# Ethernet_Switch.net
KiCad netlist of a schematic drawn in Altium Designer
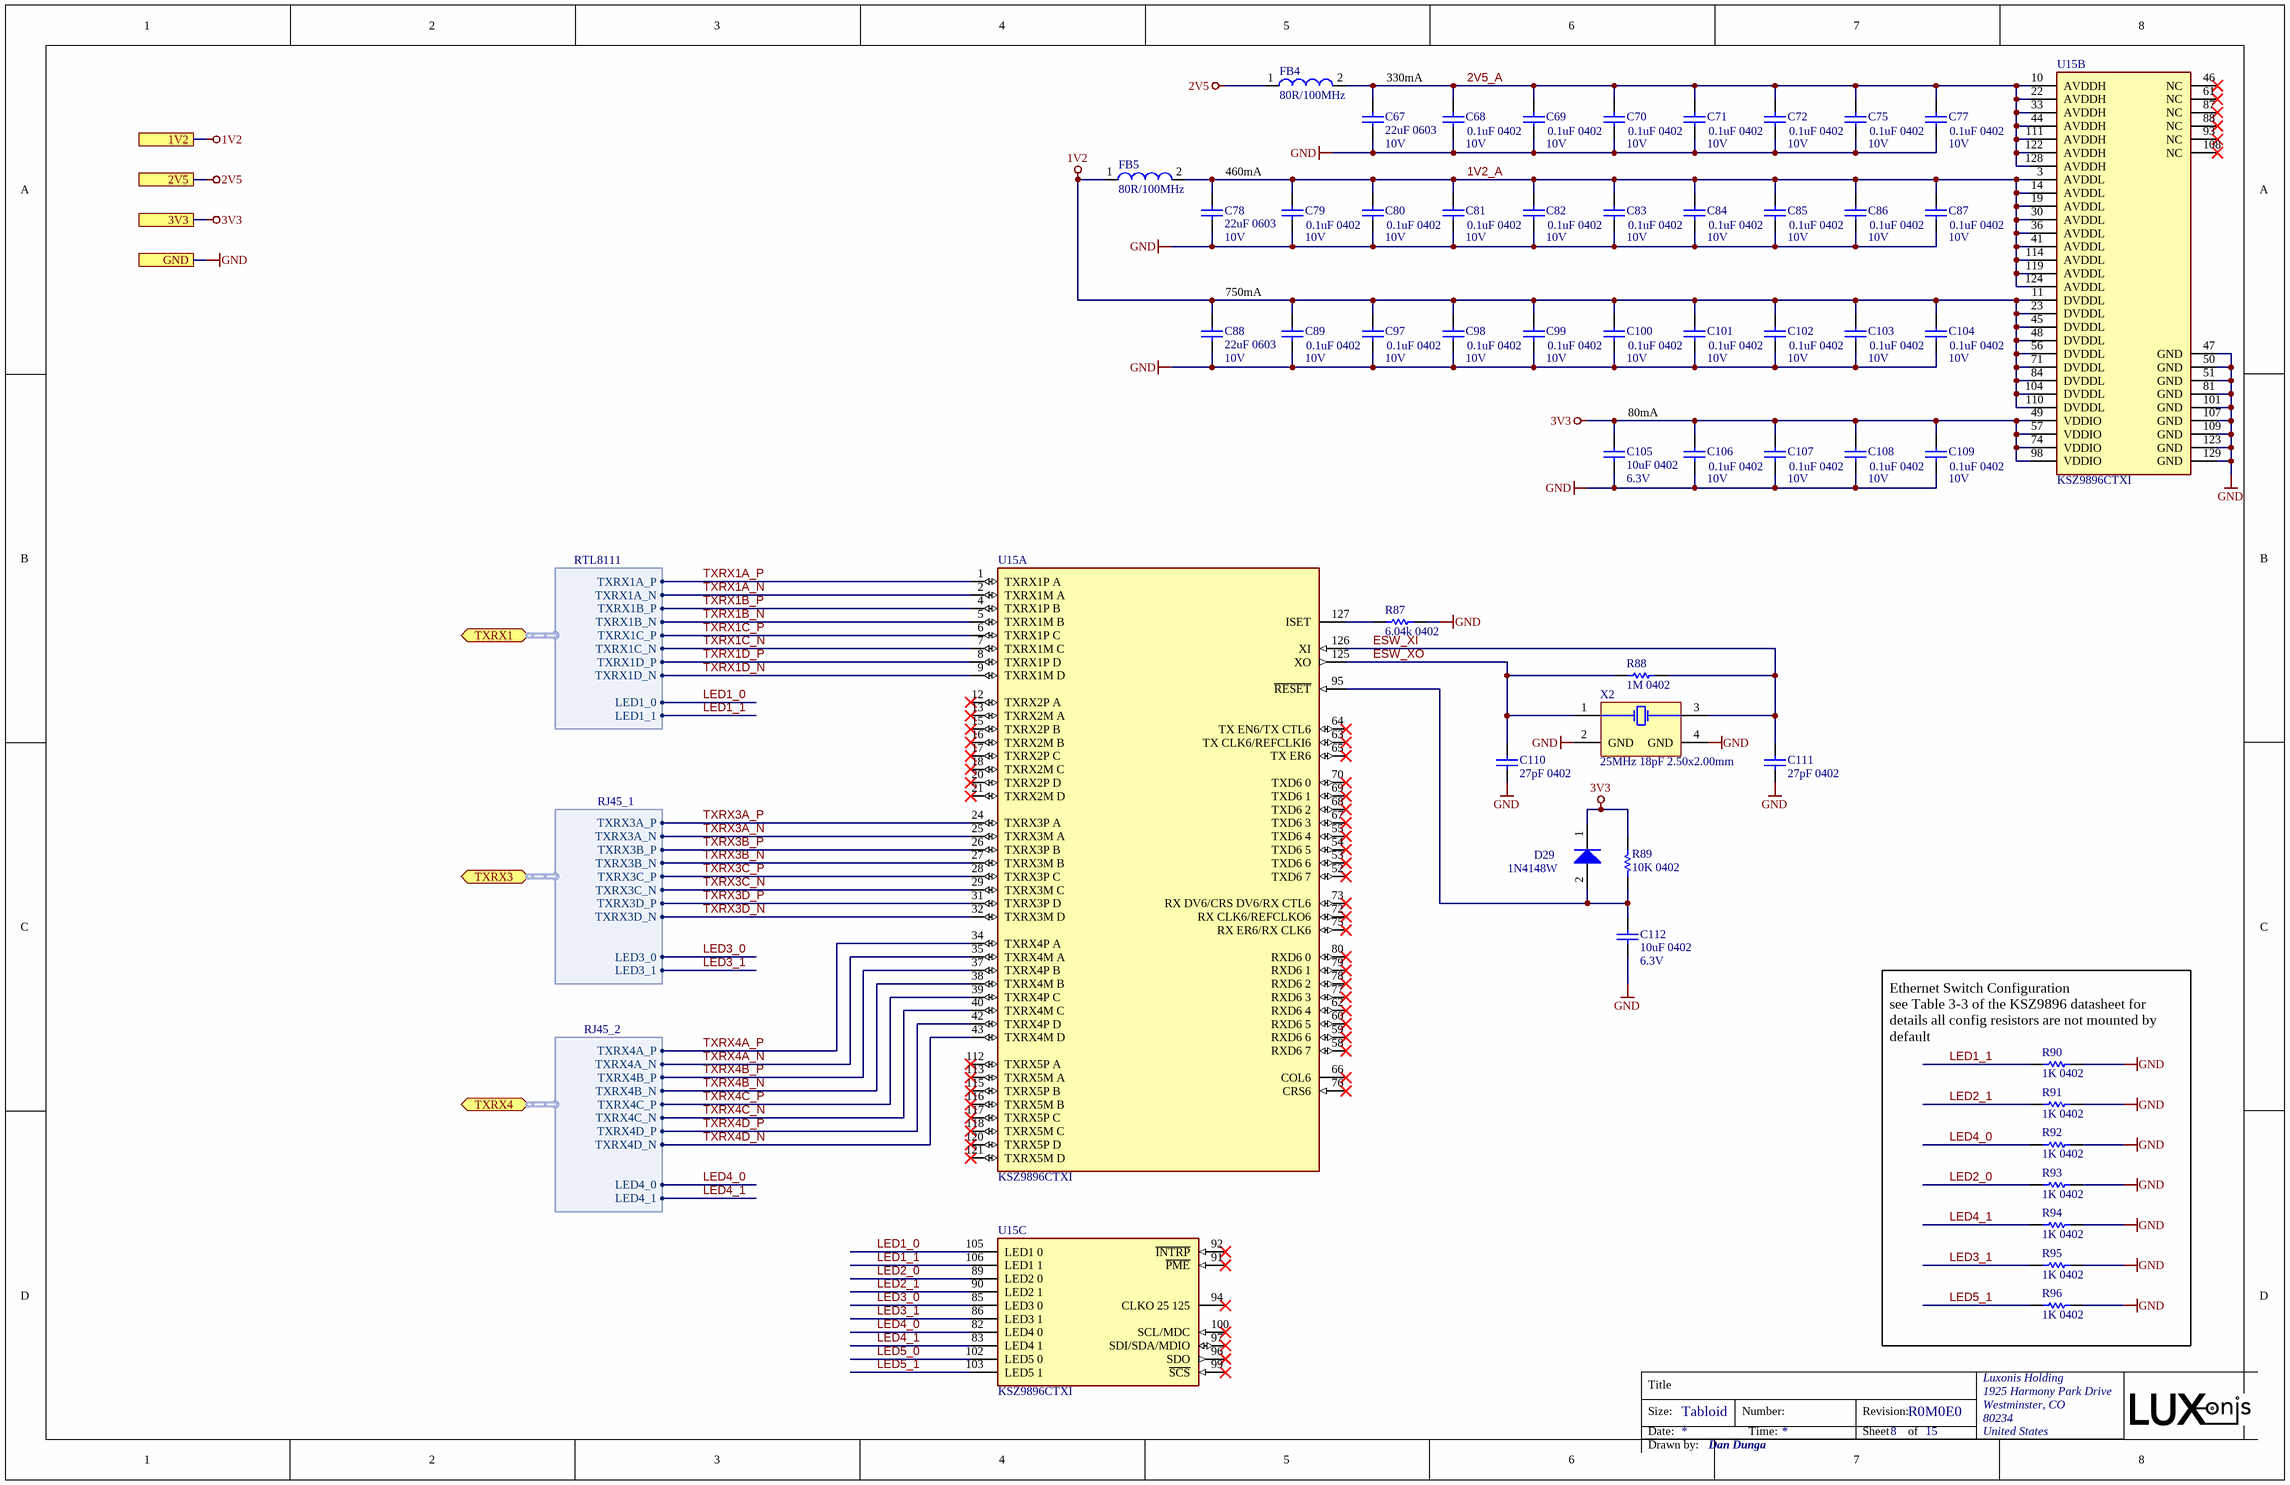
[diagram p0: Ethernet_Switch.SchDoc]

(export (version "E")
  (design (tool "Eeschema 10.0.6"))
  (components
    (comp (ref "C67")
      (value "22uF 0603")
      (footprint "CAPC0603(1608)100_N")
      (description "CAP CER 22UF 10V X5R 0603 20%")
      (fields (field (name "TOLERANCE") "20%") (field (name "VOLTAGE RATING") "10V"))
      (libsource (lib "LuxonisMaster") (part "GRM188R61A226ME15D"))
    )
    (comp (ref "C68")
      (value "0.1uF 0402")
      (footprint "CAPC0402(1005)70_N")
      (description "CAP CER 0.1UF 10V X7R 0402 5%")
      (fields (field (name "TOLERANCE") "5%") (field (name "VOLTAGE RATING") "10V"))
      (libsource (lib "LuxonisMaster") (part "GRM155R71A104JA01D"))
    )
    (comp (ref "C69")
      (value "0.1uF 0402")
      (footprint "CAPC0402(1005)70_N")
      (description "CAP CER 0.1UF 10V X7R 0402 5%")
      (fields (field (name "TOLERANCE") "5%") (field (name "VOLTAGE RATING") "10V"))
      (libsource (lib "LuxonisMaster") (part "GRM155R71A104JA01D"))
    )
    (comp (ref "C70")
      (value "0.1uF 0402")
      (footprint "CAPC0402(1005)70_N")
      (description "CAP CER 0.1UF 10V X7R 0402 5%")
      (fields (field (name "TOLERANCE") "5%") (field (name "VOLTAGE RATING") "10V"))
      (libsource (lib "LuxonisMaster") (part "GRM155R71A104JA01D"))
    )
    (comp (ref "C71")
      (value "0.1uF 0402")
      (footprint "CAPC0402(1005)70_N")
      (description "CAP CER 0.1UF 10V X7R 0402 5%")
      (fields (field (name "TOLERANCE") "5%") (field (name "VOLTAGE RATING") "10V"))
      (libsource (lib "LuxonisMaster") (part "GRM155R71A104JA01D"))
    )
    (comp (ref "C72")
      (value "0.1uF 0402")
      (footprint "CAPC0402(1005)70_N")
      (description "CAP CER 0.1UF 10V X7R 0402 5%")
      (fields (field (name "TOLERANCE") "5%") (field (name "VOLTAGE RATING") "10V"))
      (libsource (lib "LuxonisMaster") (part "GRM155R71A104JA01D"))
    )
    (comp (ref "C75")
      (value "0.1uF 0402")
      (footprint "CAPC0402(1005)70_N")
      (description "CAP CER 0.1UF 10V X7R 0402 5%")
      (fields (field (name "TOLERANCE") "5%") (field (name "VOLTAGE RATING") "10V"))
      (libsource (lib "LuxonisMaster") (part "GRM155R71A104JA01D"))
    )
    (comp (ref "C77")
      (value "0.1uF 0402")
      (footprint "CAPC0402(1005)70_N")
      (description "CAP CER 0.1UF 10V X7R 0402 5%")
      (fields (field (name "TOLERANCE") "5%") (field (name "VOLTAGE RATING") "10V"))
      (libsource (lib "LuxonisMaster") (part "GRM155R71A104JA01D"))
    )
    (comp (ref "C78")
      (value "22uF 0603")
      (footprint "CAPC0603(1608)100_N")
      (description "CAP CER 22UF 10V X5R 0603 20%")
      (fields (field (name "TOLERANCE") "20%") (field (name "VOLTAGE RATING") "10V"))
      (libsource (lib "LuxonisMaster") (part "GRM188R61A226ME15D"))
    )
    (comp (ref "C79")
      (value "0.1uF 0402")
      (footprint "CAPC0402(1005)70_N")
      (description "CAP CER 0.1UF 10V X7R 0402 5%")
      (fields (field (name "TOLERANCE") "5%") (field (name "VOLTAGE RATING") "10V"))
      (libsource (lib "LuxonisMaster") (part "GRM155R71A104JA01D"))
    )
    (comp (ref "C80")
      (value "0.1uF 0402")
      (footprint "CAPC0402(1005)70_N")
      (description "CAP CER 0.1UF 10V X7R 0402 5%")
      (fields (field (name "TOLERANCE") "5%") (field (name "VOLTAGE RATING") "10V"))
      (libsource (lib "LuxonisMaster") (part "GRM155R71A104JA01D"))
    )
    (comp (ref "C81")
      (value "0.1uF 0402")
      (footprint "CAPC0402(1005)70_N")
      (description "CAP CER 0.1UF 10V X7R 0402 5%")
      (fields (field (name "TOLERANCE") "5%") (field (name "VOLTAGE RATING") "10V"))
      (libsource (lib "LuxonisMaster") (part "GRM155R71A104JA01D"))
    )
    (comp (ref "C82")
      (value "0.1uF 0402")
      (footprint "CAPC0402(1005)70_N")
      (description "CAP CER 0.1UF 10V X7R 0402 5%")
      (fields (field (name "TOLERANCE") "5%") (field (name "VOLTAGE RATING") "10V"))
      (libsource (lib "LuxonisMaster") (part "GRM155R71A104JA01D"))
    )
    (comp (ref "C83")
      (value "0.1uF 0402")
      (footprint "CAPC0402(1005)70_N")
      (description "CAP CER 0.1UF 10V X7R 0402 5%")
      (fields (field (name "TOLERANCE") "5%") (field (name "VOLTAGE RATING") "10V"))
      (libsource (lib "LuxonisMaster") (part "GRM155R71A104JA01D"))
    )
    (comp (ref "C84")
      (value "0.1uF 0402")
      (footprint "CAPC0402(1005)70_N")
      (description "CAP CER 0.1UF 10V X7R 0402 5%")
      (fields (field (name "TOLERANCE") "5%") (field (name "VOLTAGE RATING") "10V"))
      (libsource (lib "LuxonisMaster") (part "GRM155R71A104JA01D"))
    )
    (comp (ref "C85")
      (value "0.1uF 0402")
      (footprint "CAPC0402(1005)70_N")
      (description "CAP CER 0.1UF 10V X7R 0402 5%")
      (fields (field (name "TOLERANCE") "5%") (field (name "VOLTAGE RATING") "10V"))
      (libsource (lib "LuxonisMaster") (part "GRM155R71A104JA01D"))
    )
    (comp (ref "C86")
      (value "0.1uF 0402")
      (footprint "CAPC0402(1005)70_N")
      (description "CAP CER 0.1UF 10V X7R 0402 5%")
      (fields (field (name "TOLERANCE") "5%") (field (name "VOLTAGE RATING") "10V"))
      (libsource (lib "LuxonisMaster") (part "GRM155R71A104JA01D"))
    )
    (comp (ref "C87")
      (value "0.1uF 0402")
      (footprint "CAPC0402(1005)70_N")
      (description "CAP CER 0.1UF 10V X7R 0402 5%")
      (fields (field (name "TOLERANCE") "5%") (field (name "VOLTAGE RATING") "10V"))
      (libsource (lib "LuxonisMaster") (part "GRM155R71A104JA01D"))
    )
    (comp (ref "C88")
      (value "22uF 0603")
      (footprint "CAPC0603(1608)100_N")
      (description "CAP CER 22UF 10V X5R 0603 20%")
      (fields (field (name "TOLERANCE") "20%") (field (name "VOLTAGE RATING") "10V"))
      (libsource (lib "LuxonisMaster") (part "GRM188R61A226ME15D"))
    )
    (comp (ref "C89")
      (value "0.1uF 0402")
      (footprint "CAPC0402(1005)70_N")
      (description "CAP CER 0.1UF 10V X7R 0402 5%")
      (fields (field (name "TOLERANCE") "5%") (field (name "VOLTAGE RATING") "10V"))
      (libsource (lib "LuxonisMaster") (part "GRM155R71A104JA01D"))
    )
    (comp (ref "C97")
      (value "0.1uF 0402")
      (footprint "CAPC0402(1005)70_N")
      (description "CAP CER 0.1UF 10V X7R 0402 5%")
      (fields (field (name "TOLERANCE") "5%") (field (name "VOLTAGE RATING") "10V"))
      (libsource (lib "LuxonisMaster") (part "GRM155R71A104JA01D"))
    )
    (comp (ref "C98")
      (value "0.1uF 0402")
      (footprint "CAPC0402(1005)70_N")
      (description "CAP CER 0.1UF 10V X7R 0402 5%")
      (fields (field (name "TOLERANCE") "5%") (field (name "VOLTAGE RATING") "10V"))
      (libsource (lib "LuxonisMaster") (part "GRM155R71A104JA01D"))
    )
    (comp (ref "C99")
      (value "0.1uF 0402")
      (footprint "CAPC0402(1005)70_N")
      (description "CAP CER 0.1UF 10V X7R 0402 5%")
      (fields (field (name "TOLERANCE") "5%") (field (name "VOLTAGE RATING") "10V"))
      (libsource (lib "LuxonisMaster") (part "GRM155R71A104JA01D"))
    )
    (comp (ref "C100")
      (value "0.1uF 0402")
      (footprint "CAPC0402(1005)70_N")
      (description "CAP CER 0.1UF 10V X7R 0402 5%")
      (fields (field (name "TOLERANCE") "5%") (field (name "VOLTAGE RATING") "10V"))
      (libsource (lib "LuxonisMaster") (part "GRM155R71A104JA01D"))
    )
    (comp (ref "C101")
      (value "0.1uF 0402")
      (footprint "CAPC0402(1005)70_N")
      (description "CAP CER 0.1UF 10V X7R 0402 5%")
      (fields (field (name "TOLERANCE") "5%") (field (name "VOLTAGE RATING") "10V"))
      (libsource (lib "LuxonisMaster") (part "GRM155R71A104JA01D"))
    )
    (comp (ref "C102")
      (value "0.1uF 0402")
      (footprint "CAPC0402(1005)70_N")
      (description "CAP CER 0.1UF 10V X7R 0402 5%")
      (fields (field (name "TOLERANCE") "5%") (field (name "VOLTAGE RATING") "10V"))
      (libsource (lib "LuxonisMaster") (part "GRM155R71A104JA01D"))
    )
    (comp (ref "C103")
      (value "0.1uF 0402")
      (footprint "CAPC0402(1005)70_N")
      (description "CAP CER 0.1UF 10V X7R 0402 5%")
      (fields (field (name "TOLERANCE") "5%") (field (name "VOLTAGE RATING") "10V"))
      (libsource (lib "LuxonisMaster") (part "GRM155R71A104JA01D"))
    )
    (comp (ref "C104")
      (value "0.1uF 0402")
      (footprint "CAPC0402(1005)70_N")
      (description "CAP CER 0.1UF 10V X7R 0402 5%")
      (fields (field (name "TOLERANCE") "5%") (field (name "VOLTAGE RATING") "10V"))
      (libsource (lib "LuxonisMaster") (part "GRM155R71A104JA01D"))
    )
    (comp (ref "C105")
      (value "10uF 0402")
      (footprint "CAPC0402(1005)70_N")
      (description "CAP CER 10UF 6.3V X5R 0402 20%")
      (fields (field (name "TOLERANCE") "20%") (field (name "VOLTAGE RATING") "6.3V"))
      (libsource (lib "LuxonisMaster") (part "GRM155R60J106ME15D"))
    )
    (comp (ref "C106")
      (value "0.1uF 0402")
      (footprint "CAPC0402(1005)70_N")
      (description "CAP CER 0.1UF 10V X7R 0402 5%")
      (fields (field (name "TOLERANCE") "5%") (field (name "VOLTAGE RATING") "10V"))
      (libsource (lib "LuxonisMaster") (part "GRM155R71A104JA01D"))
    )
    (comp (ref "C107")
      (value "0.1uF 0402")
      (footprint "CAPC0402(1005)70_N")
      (description "CAP CER 0.1UF 10V X7R 0402 5%")
      (fields (field (name "TOLERANCE") "5%") (field (name "VOLTAGE RATING") "10V"))
      (libsource (lib "LuxonisMaster") (part "GRM155R71A104JA01D"))
    )
    (comp (ref "C108")
      (value "0.1uF 0402")
      (footprint "CAPC0402(1005)70_N")
      (description "CAP CER 0.1UF 10V X7R 0402 5%")
      (fields (field (name "TOLERANCE") "5%") (field (name "VOLTAGE RATING") "10V"))
      (libsource (lib "LuxonisMaster") (part "GRM155R71A104JA01D"))
    )
    (comp (ref "C109")
      (value "0.1uF 0402")
      (footprint "CAPC0402(1005)70_N")
      (description "CAP CER 0.1UF 10V X7R 0402 5%")
      (fields (field (name "TOLERANCE") "5%") (field (name "VOLTAGE RATING") "10V"))
      (libsource (lib "LuxonisMaster") (part "GRM155R71A104JA01D"))
    )
    (comp (ref "C110")
      (value "27pF 0402")
      (footprint "CAPC0402(1005)60_N")
      (description "CAP CER 27PF 50V C0G/NP0 0402")
      (fields (field (name "TOLERANCE") "5%") (field (name "VOLTAGE") "50V"))
      (libsource (lib "BW2098POE") (part "C0402C270J5GACTU"))
    )
    (comp (ref "C111")
      (value "27pF 0402")
      (footprint "CAPC0402(1005)60_N")
      (description "CAP CER 27PF 50V C0G/NP0 0402")
      (fields (field (name "TOLERANCE") "5%") (field (name "VOLTAGE") "50V"))
      (libsource (lib "BW2098POE") (part "C0402C270J5GACTU"))
    )
    (comp (ref "C112")
      (value "10uF 0402")
      (footprint "CAPC0402(1005)70_N")
      (description "CAP CER 10UF 6.3V X5R 0402 20%")
      (fields (field (name "TOLERANCE") "20%") (field (name "VOLTAGE RATING") "6.3V"))
      (libsource (lib "LuxonisMaster") (part "GRM155R60J106ME15D"))
    )
    (comp (ref "D29")
      (value "1N4148W")
      (footprint "1N4148W-7-F")
      (description "DIODE GEN PURP 100V 300MA SOD123")
      (fields (field (name "VOLTAGE") "100V"))
      (libsource (lib "PCBProject") (part "1N4148W-7-F"))
    )
    (comp (ref "FB4")
      (value "80R/100MHz")
      (footprint "BK1608HS800-T_N")
      (description "FERRITE BEAD 80 OHM 0603 1LN")
      (fields (field (name "TOLERANCE") "25%"))
      (libsource (lib "LuxonisMaster") (part "BK1608HS800-T"))
    )
    (comp (ref "FB5")
      (value "80R/100MHz")
      (footprint "BK1608HS800-T_N")
      (description "FERRITE BEAD 80 OHM 0603 1LN")
      (fields (field (name "TOLERANCE") "25%"))
      (libsource (lib "LuxonisMaster") (part "BK1608HS800-T"))
    )
    (comp (ref "R87")
      (value "6.04k 0402")
      (footprint "RESC0402(1005)_L")
      (description "Res Thick Film 0402 6.04K Ohm 1% 0.063W(1/16W) ±100ppm/C Molded SMD Automotive Paper T/R")
      (fields (field (name "TOLERANCE") "1%"))
      (libsource (lib "BW2098POE_Anfa") (part "CRCW04026K04FKED"))
    )
    (comp (ref "R88")
      (value "1M 0402")
      (footprint "RESC0402(1005)_N")
      (description "RES SMD 1M OHM 1% 1/16W 0402")
      (fields (field (name "TOLERANCE") "1%"))
      (libsource (lib "LuxonisMaster") (part "RC0402FR-071ML"))
    )
    (comp (ref "R89")
      (value "10K 0402")
      (footprint "RESC0402(1005)_N")
      (fields (field (name "TOLERANCE") "1%"))
      (libsource (lib "LuxonisMaster") (part "RC0402FR-1310KL"))
    )
    (comp (ref "R90")
      (value "1K 0402")
      (footprint "RESC0402(1005)_N")
      (fields (field (name "TOLERANCE") "1%"))
      (libsource (lib "LuxonisMaster") (part "RC0402FR-071KL"))
    )
    (comp (ref "R91")
      (value "1K 0402")
      (footprint "RESC0402(1005)_N")
      (fields (field (name "TOLERANCE") "1%"))
      (libsource (lib "LuxonisMaster") (part "RC0402FR-071KL"))
    )
    (comp (ref "R92")
      (value "1K 0402")
      (footprint "RESC0402(1005)_N")
      (fields (field (name "TOLERANCE") "1%"))
      (libsource (lib "LuxonisMaster") (part "RC0402FR-071KL"))
    )
    (comp (ref "R93")
      (value "1K 0402")
      (footprint "RESC0402(1005)_N")
      (fields (field (name "TOLERANCE") "1%"))
      (libsource (lib "LuxonisMaster") (part "RC0402FR-071KL"))
    )
    (comp (ref "R94")
      (value "1K 0402")
      (footprint "RESC0402(1005)_N")
      (fields (field (name "TOLERANCE") "1%"))
      (libsource (lib "LuxonisMaster") (part "RC0402FR-071KL"))
    )
    (comp (ref "R95")
      (value "1K 0402")
      (footprint "RESC0402(1005)_N")
      (fields (field (name "TOLERANCE") "1%"))
      (libsource (lib "LuxonisMaster") (part "RC0402FR-071KL"))
    )
    (comp (ref "R96")
      (value "1K 0402")
      (footprint "RESC0402(1005)_N")
      (fields (field (name "TOLERANCE") "1%"))
      (libsource (lib "LuxonisMaster") (part "RC0402FR-071KL"))
    )
    (comp (ref "U15")
      (value "KSZ9896CTXI")
      (footprint "FP-C04-418-IPC_A")
      (description "MICROCHIP - KSZ9896CTXI - ETHERNET SWITCH, 1GBPS, -40 TO 85DEG C")
      (libsource (lib "BW2098POE_Anfa") (part "KSZ9896CTXI"))
    )
    (comp (ref "X2")
      (value "25MHz 18pF 2.50x2.00mm")
      (footprint "ECS-250-18-36B-CKY-TR")
      (description "CRYSTAL 25.0000MHZ 18PF SMD 25MHz ±10ppm Crystal 18pF 50 Ohms 4-SMD, No Lead")
      (libsource (lib "BW2098POE") (part "ECS-250-18-36B-CKY-TR"))
    )
  )
  (nets
    (net (code "4") (name "/1V2_A") (class "Default")
      (node (ref "C78") (pin "2") (pinfunction "2_2") (pintype "passive"))
      (node (ref "C79") (pin "2") (pinfunction "2_2") (pintype "passive"))
      (node (ref "C80") (pin "2") (pinfunction "2_2") (pintype "passive"))
      (node (ref "C81") (pin "2") (pinfunction "2_2") (pintype "passive"))
      (node (ref "C82") (pin "2") (pinfunction "2_2") (pintype "passive"))
      (node (ref "C83") (pin "2") (pinfunction "2_2") (pintype "passive"))
      (node (ref "C84") (pin "2") (pinfunction "2_2") (pintype "passive"))
      (node (ref "C85") (pin "2") (pinfunction "2_2") (pintype "passive"))
      (node (ref "C86") (pin "2") (pinfunction "2_2") (pintype "passive"))
      (node (ref "C87") (pin "2") (pinfunction "2_2") (pintype "passive"))
      (node (ref "FB5") (pin "2") (pinfunction "2_2") (pintype "passive"))
      (node (ref "U15") (pin "114") (pinfunction "AVDDL_114") (pintype "power_in"))
      (node (ref "U15") (pin "119") (pinfunction "AVDDL_119") (pintype "power_in"))
      (node (ref "U15") (pin "124") (pinfunction "AVDDL_124") (pintype "power_in"))
      (node (ref "U15") (pin "14") (pinfunction "AVDDL_14") (pintype "power_in"))
      (node (ref "U15") (pin "19") (pinfunction "AVDDL_19") (pintype "power_in"))
      (node (ref "U15") (pin "3") (pinfunction "AVDDL_3") (pintype "power_in"))
      (node (ref "U15") (pin "30") (pinfunction "AVDDL_30") (pintype "power_in"))
      (node (ref "U15") (pin "36") (pinfunction "AVDDL_36") (pintype "passive"))
      (node (ref "U15") (pin "41") (pinfunction "AVDDL_41") (pintype "power_in"))
    )
    (net (code "5") (name "/2V5_A") (class "Default")
      (node (ref "C67") (pin "2") (pinfunction "2_2") (pintype "passive"))
      (node (ref "C68") (pin "2") (pinfunction "2_2") (pintype "passive"))
      (node (ref "C69") (pin "2") (pinfunction "2_2") (pintype "passive"))
      (node (ref "C70") (pin "2") (pinfunction "2_2") (pintype "passive"))
      (node (ref "C71") (pin "2") (pinfunction "2_2") (pintype "passive"))
      (node (ref "C72") (pin "2") (pinfunction "2_2") (pintype "passive"))
      (node (ref "C75") (pin "2") (pinfunction "2_2") (pintype "passive"))
      (node (ref "C77") (pin "2") (pinfunction "2_2") (pintype "passive"))
      (node (ref "FB4") (pin "2") (pinfunction "2_2") (pintype "passive"))
      (node (ref "U15") (pin "10") (pinfunction "AVDDH_10") (pintype "power_in"))
      (node (ref "U15") (pin "111") (pinfunction "AVDDH_111") (pintype "power_in"))
      (node (ref "U15") (pin "122") (pinfunction "AVDDH_122") (pintype "power_in"))
      (node (ref "U15") (pin "128") (pinfunction "AVDDH_128") (pintype "power_in"))
      (node (ref "U15") (pin "22") (pinfunction "AVDDH_22") (pintype "power_in"))
      (node (ref "U15") (pin "33") (pinfunction "AVDDH_33") (pintype "power_in"))
      (node (ref "U15") (pin "44") (pinfunction "AVDDH_44") (pintype "power_in"))
    )
    (net (code "6") (name "/ESW_XI") (class "Default")
      (node (ref "C111") (pin "2") (pinfunction "2_2") (pintype "passive"))
      (node (ref "R88") (pin "2") (pinfunction "2_2") (pintype "passive"))
      (node (ref "U15") (pin "126") (pinfunction "XI_126") (pintype "input"))
      (node (ref "X2") (pin "3") (pinfunction "X2_3") (pintype "passive"))
    )
    (net (code "7") (name "/ESW_XO") (class "Default")
      (node (ref "C110") (pin "2") (pinfunction "2_2") (pintype "passive"))
      (node (ref "R88") (pin "1") (pinfunction "1_1") (pintype "passive"))
      (node (ref "U15") (pin "125") (pinfunction "XO_125") (pintype "output"))
      (node (ref "X2") (pin "1") (pinfunction "X1_1") (pintype "passive"))
    )
    (net (code "8") (name "/LED1_0") (class "Default")
      (node (ref "U15") (pin "105") (pinfunction "LED1_0_105") (pintype "passive"))
    )
    (net (code "9") (name "/LED1_1") (class "Default")
      (node (ref "R90") (pin "2") (pinfunction "2_2") (pintype "passive"))
      (node (ref "U15") (pin "106") (pinfunction "LED1_1_106") (pintype "passive"))
    )
    (net (code "10") (name "/LED2_0") (class "Default")
      (node (ref "R93") (pin "2") (pinfunction "2_2") (pintype "passive"))
      (node (ref "U15") (pin "89") (pinfunction "LED2_0_89") (pintype "passive"))
    )
    (net (code "11") (name "/LED2_1") (class "Default")
      (node (ref "R91") (pin "2") (pinfunction "2_2") (pintype "passive"))
      (node (ref "U15") (pin "90") (pinfunction "LED2_1_90") (pintype "passive"))
    )
    (net (code "12") (name "/LED3_0") (class "Default")
      (node (ref "U15") (pin "85") (pinfunction "LED3_0_85") (pintype "passive"))
    )
    (net (code "13") (name "/LED3_1") (class "Default")
      (node (ref "R95") (pin "2") (pinfunction "2_2") (pintype "passive"))
      (node (ref "U15") (pin "86") (pinfunction "LED3_1_86") (pintype "passive"))
    )
    (net (code "14") (name "/LED4_0") (class "Default")
      (node (ref "R92") (pin "2") (pinfunction "2_2") (pintype "passive"))
      (node (ref "U15") (pin "82") (pinfunction "LED4_0_82") (pintype "passive"))
    )
    (net (code "15") (name "/LED4_1") (class "Default")
      (node (ref "R94") (pin "2") (pinfunction "2_2") (pintype "passive"))
      (node (ref "U15") (pin "83") (pinfunction "LED4_1_83") (pintype "passive"))
    )
    (net (code "16") (name "/LED5_0") (class "Default")
      (node (ref "U15") (pin "102") (pinfunction "LED5_0_102") (pintype "passive"))
    )
    (net (code "17") (name "/LED5_1") (class "Default")
      (node (ref "R96") (pin "2") (pinfunction "2_2") (pintype "passive"))
      (node (ref "U15") (pin "103") (pinfunction "LED5_1_103") (pintype "passive"))
    )
    (net (code "18") (name "/TXRX1A_N") (class "Default")
      (node (ref "U15") (pin "2") (pinfunction "TXRX1M_A_2") (pintype "bidirectional"))
    )
    (net (code "19") (name "/TXRX1A_P") (class "Default")
      (node (ref "U15") (pin "1") (pinfunction "TXRX1P_A_1") (pintype "bidirectional"))
    )
    (net (code "20") (name "/TXRX1B_N") (class "Default")
      (node (ref "U15") (pin "5") (pinfunction "TXRX1M_B_5") (pintype "bidirectional"))
    )
    (net (code "21") (name "/TXRX1B_P") (class "Default")
      (node (ref "U15") (pin "4") (pinfunction "TXRX1P_B_4") (pintype "bidirectional"))
    )
    (net (code "22") (name "/TXRX1C_N") (class "Default")
      (node (ref "U15") (pin "7") (pinfunction "TXRX1M_C_7") (pintype "bidirectional"))
    )
    (net (code "23") (name "/TXRX1C_P") (class "Default")
      (node (ref "U15") (pin "6") (pinfunction "TXRX1P_C_6") (pintype "bidirectional"))
    )
    (net (code "24") (name "/TXRX1D_N") (class "Default")
      (node (ref "U15") (pin "9") (pinfunction "TXRX1M_D_9") (pintype "bidirectional"))
    )
    (net (code "25") (name "/TXRX1D_P") (class "Default")
      (node (ref "U15") (pin "8") (pinfunction "TXRX1P_D_8") (pintype "bidirectional"))
    )
    (net (code "26") (name "/TXRX3A_N") (class "Default")
      (node (ref "U15") (pin "25") (pinfunction "TXRX3M_A_25") (pintype "bidirectional"))
    )
    (net (code "27") (name "/TXRX3A_P") (class "Default")
      (node (ref "U15") (pin "24") (pinfunction "TXRX3P_A_24") (pintype "bidirectional"))
    )
    (net (code "28") (name "/TXRX3B_N") (class "Default")
      (node (ref "U15") (pin "27") (pinfunction "TXRX3M_B_27") (pintype "bidirectional"))
    )
    (net (code "29") (name "/TXRX3B_P") (class "Default")
      (node (ref "U15") (pin "26") (pinfunction "TXRX3P_B_26") (pintype "bidirectional"))
    )
    (net (code "30") (name "/TXRX3C_N") (class "Default")
      (node (ref "U15") (pin "29") (pinfunction "TXRX3M_C_29") (pintype "bidirectional"))
    )
    (net (code "31") (name "/TXRX3C_P") (class "Default")
      (node (ref "U15") (pin "28") (pinfunction "TXRX3P_C_28") (pintype "bidirectional"))
    )
    (net (code "32") (name "/TXRX3D_N") (class "Default")
      (node (ref "U15") (pin "32") (pinfunction "TXRX3M_D_32") (pintype "bidirectional"))
    )
    (net (code "33") (name "/TXRX3D_P") (class "Default")
      (node (ref "U15") (pin "31") (pinfunction "TXRX3P_D_31") (pintype "bidirectional"))
    )
    (net (code "34") (name "/TXRX4A_N") (class "Default")
      (node (ref "U15") (pin "35") (pinfunction "TXRX4M_A_35") (pintype "bidirectional"))
    )
    (net (code "35") (name "/TXRX4A_P") (class "Default")
      (node (ref "U15") (pin "34") (pinfunction "TXRX4P_A_34") (pintype "bidirectional"))
    )
    (net (code "36") (name "/TXRX4B_N") (class "Default")
      (node (ref "U15") (pin "38") (pinfunction "TXRX4M_B_38") (pintype "bidirectional"))
    )
    (net (code "37") (name "/TXRX4B_P") (class "Default")
      (node (ref "U15") (pin "37") (pinfunction "TXRX4P_B_37") (pintype "bidirectional"))
    )
    (net (code "38") (name "/TXRX4C_N") (class "Default")
      (node (ref "U15") (pin "40") (pinfunction "TXRX4M_C_40") (pintype "bidirectional"))
    )
    (net (code "39") (name "/TXRX4C_P") (class "Default")
      (node (ref "U15") (pin "39") (pinfunction "TXRX4P_C_39") (pintype "bidirectional"))
    )
    (net (code "40") (name "/TXRX4D_N") (class "Default")
      (node (ref "U15") (pin "43") (pinfunction "TXRX4M_D_43") (pintype "bidirectional"))
    )
    (net (code "41") (name "/TXRX4D_P") (class "Default")
      (node (ref "U15") (pin "42") (pinfunction "TXRX4P_D_42") (pintype "bidirectional"))
    )
    (net (code "45") (name "1V2") (class "Default")
      (node (ref "C100") (pin "2") (pinfunction "2_2") (pintype "passive"))
      (node (ref "C101") (pin "2") (pinfunction "2_2") (pintype "passive"))
      (node (ref "C102") (pin "2") (pinfunction "2_2") (pintype "passive"))
      (node (ref "C103") (pin "2") (pinfunction "2_2") (pintype "passive"))
      (node (ref "C104") (pin "2") (pinfunction "2_2") (pintype "passive"))
      (node (ref "C88") (pin "2") (pinfunction "2_2") (pintype "passive"))
      (node (ref "C89") (pin "2") (pinfunction "2_2") (pintype "passive"))
      (node (ref "C97") (pin "2") (pinfunction "2_2") (pintype "passive"))
      (node (ref "C98") (pin "2") (pinfunction "2_2") (pintype "passive"))
      (node (ref "C99") (pin "2") (pinfunction "2_2") (pintype "passive"))
      (node (ref "FB5") (pin "1") (pinfunction "1_1") (pintype "passive"))
      (node (ref "U15") (pin "104") (pinfunction "DVDDL_104") (pintype "power_in"))
      (node (ref "U15") (pin "11") (pinfunction "DVDDL_11") (pintype "power_in"))
      (node (ref "U15") (pin "110") (pinfunction "DVDDL_110") (pintype "power_in"))
      (node (ref "U15") (pin "23") (pinfunction "DVDDL_23") (pintype "power_in"))
      (node (ref "U15") (pin "45") (pinfunction "DVDDL_45") (pintype "power_in"))
      (node (ref "U15") (pin "48") (pinfunction "DVDDL_48") (pintype "power_in"))
      (node (ref "U15") (pin "56") (pinfunction "DVDDL_56") (pintype "power_in"))
      (node (ref "U15") (pin "71") (pinfunction "DVDDL_71") (pintype "power_in"))
      (node (ref "U15") (pin "84") (pinfunction "DVDDL_84") (pintype "power_in"))
    )
    (net (code "46") (name "2V5") (class "Default")
      (node (ref "FB4") (pin "1") (pinfunction "1_1") (pintype "passive"))
    )
    (net (code "47") (name "3V3") (class "Default")
      (node (ref "C105") (pin "2") (pinfunction "2_2") (pintype "passive"))
      (node (ref "C106") (pin "2") (pinfunction "2_2") (pintype "passive"))
      (node (ref "C107") (pin "2") (pinfunction "2_2") (pintype "passive"))
      (node (ref "C108") (pin "2") (pinfunction "2_2") (pintype "passive"))
      (node (ref "C109") (pin "2") (pinfunction "2_2") (pintype "passive"))
      (node (ref "D29") (pin "1") (pinfunction "K_1") (pintype "passive"))
      (node (ref "R89") (pin "1") (pinfunction "1_1") (pintype "passive"))
      (node (ref "U15") (pin "49") (pinfunction "VDDIO_49") (pintype "power_in"))
      (node (ref "U15") (pin "57") (pinfunction "VDDIO_57") (pintype "power_in"))
      (node (ref "U15") (pin "74") (pinfunction "VDDIO_74") (pintype "power_in"))
      (node (ref "U15") (pin "98") (pinfunction "VDDIO_98") (pintype "power_in"))
    )
    (net (code "48") (name "GND") (class "Default")
      (node (ref "C100") (pin "1") (pinfunction "1_1") (pintype "passive"))
      (node (ref "C101") (pin "1") (pinfunction "1_1") (pintype "passive"))
      (node (ref "C102") (pin "1") (pinfunction "1_1") (pintype "passive"))
      (node (ref "C103") (pin "1") (pinfunction "1_1") (pintype "passive"))
      (node (ref "C104") (pin "1") (pinfunction "1_1") (pintype "passive"))
      (node (ref "C105") (pin "1") (pinfunction "1_1") (pintype "passive"))
      (node (ref "C106") (pin "1") (pinfunction "1_1") (pintype "passive"))
      (node (ref "C107") (pin "1") (pinfunction "1_1") (pintype "passive"))
      (node (ref "C108") (pin "1") (pinfunction "1_1") (pintype "passive"))
      (node (ref "C109") (pin "1") (pinfunction "1_1") (pintype "passive"))
      (node (ref "C110") (pin "1") (pinfunction "1_1") (pintype "passive"))
      (node (ref "C111") (pin "1") (pinfunction "1_1") (pintype "passive"))
      (node (ref "C112") (pin "1") (pinfunction "1_1") (pintype "passive"))
      (node (ref "C67") (pin "1") (pinfunction "1_1") (pintype "passive"))
      (node (ref "C68") (pin "1") (pinfunction "1_1") (pintype "passive"))
      (node (ref "C69") (pin "1") (pinfunction "1_1") (pintype "passive"))
      (node (ref "C70") (pin "1") (pinfunction "1_1") (pintype "passive"))
      (node (ref "C71") (pin "1") (pinfunction "1_1") (pintype "passive"))
      (node (ref "C72") (pin "1") (pinfunction "1_1") (pintype "passive"))
      (node (ref "C75") (pin "1") (pinfunction "1_1") (pintype "passive"))
      (node (ref "C77") (pin "1") (pinfunction "1_1") (pintype "passive"))
      (node (ref "C78") (pin "1") (pinfunction "1_1") (pintype "passive"))
      (node (ref "C79") (pin "1") (pinfunction "1_1") (pintype "passive"))
      (node (ref "C80") (pin "1") (pinfunction "1_1") (pintype "passive"))
      (node (ref "C81") (pin "1") (pinfunction "1_1") (pintype "passive"))
      (node (ref "C82") (pin "1") (pinfunction "1_1") (pintype "passive"))
      (node (ref "C83") (pin "1") (pinfunction "1_1") (pintype "passive"))
      (node (ref "C84") (pin "1") (pinfunction "1_1") (pintype "passive"))
      (node (ref "C85") (pin "1") (pinfunction "1_1") (pintype "passive"))
      (node (ref "C86") (pin "1") (pinfunction "1_1") (pintype "passive"))
      (node (ref "C87") (pin "1") (pinfunction "1_1") (pintype "passive"))
      (node (ref "C88") (pin "1") (pinfunction "1_1") (pintype "passive"))
      (node (ref "C89") (pin "1") (pinfunction "1_1") (pintype "passive"))
      (node (ref "C97") (pin "1") (pinfunction "1_1") (pintype "passive"))
      (node (ref "C98") (pin "1") (pinfunction "1_1") (pintype "passive"))
      (node (ref "C99") (pin "1") (pinfunction "1_1") (pintype "passive"))
      (node (ref "R87") (pin "2") (pinfunction "2_2") (pintype "passive"))
      (node (ref "R90") (pin "1") (pinfunction "1_1") (pintype "passive"))
      (node (ref "R91") (pin "1") (pinfunction "1_1") (pintype "passive"))
      (node (ref "R92") (pin "1") (pinfunction "1_1") (pintype "passive"))
      (node (ref "R93") (pin "1") (pinfunction "1_1") (pintype "passive"))
      (node (ref "R94") (pin "1") (pinfunction "1_1") (pintype "passive"))
      (node (ref "R95") (pin "1") (pinfunction "1_1") (pintype "passive"))
      (node (ref "R96") (pin "1") (pinfunction "1_1") (pintype "passive"))
      (node (ref "U15") (pin "101") (pinfunction "GND_101") (pintype "power_in"))
      (node (ref "U15") (pin "107") (pinfunction "GND_107") (pintype "power_in"))
      (node (ref "U15") (pin "109") (pinfunction "GND_109") (pintype "power_in"))
      (node (ref "U15") (pin "123") (pinfunction "GND_123") (pintype "power_in"))
      (node (ref "U15") (pin "129") (pinfunction "GND_129") (pintype "power_in"))
      (node (ref "U15") (pin "47") (pinfunction "GND_47") (pintype "power_in"))
      (node (ref "U15") (pin "50") (pinfunction "GND_50") (pintype "power_in"))
      (node (ref "U15") (pin "51") (pinfunction "GND_51") (pintype "power_in"))
      (node (ref "U15") (pin "81") (pinfunction "GND_81") (pintype "power_in"))
      (node (ref "X2") (pin "2") (pinfunction "GND_2") (pintype "power_in"))
      (node (ref "X2") (pin "4") (pinfunction "GND_4") (pintype "power_in"))
    )
    (net (code "49") (name "Net-(D29-A)") (class "Default")
      (node (ref "C112") (pin "2") (pinfunction "2_2") (pintype "passive"))
      (node (ref "D29") (pin "2") (pinfunction "A_2") (pintype "passive"))
      (node (ref "R89") (pin "2") (pinfunction "2_2") (pintype "passive"))
      (node (ref "U15") (pin "95") (pinfunction "~{RESET}_95") (pintype "input"))
    )
    (net (code "50") (name "Net-(U15A-ISET)") (class "Default")
      (node (ref "R87") (pin "1") (pinfunction "1_1") (pintype "passive"))
      (node (ref "U15") (pin "127") (pinfunction "ISET_127") (pintype "passive"))
    )
    (net (code "51") (name "unconnected-(U15A-COL6-Pad66)") (class "Default")
      (node (ref "U15") (pin "66") (pinfunction "COL6_66") (pintype "passive+no_connect"))
    )
    (net (code "52") (name "unconnected-(U15A-CRS6-Pad76)") (class "Default")
      (node (ref "U15") (pin "76") (pinfunction "CRS6_76") (pintype "input+no_connect"))
    )
    (net (code "53") (name "unconnected-(U15A-RXD6_0-Pad80)") (class "Default")
      (node (ref "U15") (pin "80") (pinfunction "RXD6_0_80") (pintype "bidirectional+no_connect"))
    )
    (net (code "54") (name "unconnected-(U15A-RXD6_1-Pad79)") (class "Default")
      (node (ref "U15") (pin "79") (pinfunction "RXD6_1_79") (pintype "bidirectional+no_connect"))
    )
    (net (code "55") (name "unconnected-(U15A-RXD6_2-Pad78)") (class "Default")
      (node (ref "U15") (pin "78") (pinfunction "RXD6_2_78") (pintype "bidirectional+no_connect"))
    )
    (net (code "56") (name "unconnected-(U15A-RXD6_3-Pad77)") (class "Default")
      (node (ref "U15") (pin "77") (pinfunction "RXD6_3_77") (pintype "bidirectional+no_connect"))
    )
    (net (code "57") (name "unconnected-(U15A-RXD6_4-Pad62)") (class "Default")
      (node (ref "U15") (pin "62") (pinfunction "RXD6_4_62") (pintype "bidirectional+no_connect"))
    )
    (net (code "58") (name "unconnected-(U15A-RXD6_5-Pad60)") (class "Default")
      (node (ref "U15") (pin "60") (pinfunction "RXD6_5_60") (pintype "bidirectional+no_connect"))
    )
    (net (code "59") (name "unconnected-(U15A-RXD6_6-Pad59)") (class "Default")
      (node (ref "U15") (pin "59") (pinfunction "RXD6_6_59") (pintype "bidirectional+no_connect"))
    )
    (net (code "60") (name "unconnected-(U15A-RXD6_7-Pad58)") (class "Default")
      (node (ref "U15") (pin "58") (pinfunction "RXD6_7_58") (pintype "bidirectional+no_connect"))
    )
    (net (code "61") (name "unconnected-(U15A-RX_CLK6{slash}REFCLKO6-Pad72)") (class "Default")
      (node (ref "U15") (pin "72") (pinfunction "RX_CLK6/REFCLKO6_72") (pintype "bidirectional+no_connect"))
    )
    (net (code "62") (name "unconnected-(U15A-RX_DV6{slash}CRS_DV6{slash}RX_CTL6-Pad73)") (class "Default")
      (node (ref "U15") (pin "73") (pinfunction "RX_DV6/CRS_DV6/RX_CTL6_73") (pintype "bidirectional+no_connect"))
    )
    (net (code "63") (name "unconnected-(U15A-RX_ER6{slash}RX_CLK6-Pad75)") (class "Default")
      (node (ref "U15") (pin "75") (pinfunction "RX_ER6/RX_CLK6_75") (pintype "bidirectional+no_connect"))
    )
    (net (code "64") (name "unconnected-(U15A-TXD6_0-Pad70)") (class "Default")
      (node (ref "U15") (pin "70") (pinfunction "TXD6_0_70") (pintype "bidirectional+no_connect"))
    )
    (net (code "65") (name "unconnected-(U15A-TXD6_1-Pad69)") (class "Default")
      (node (ref "U15") (pin "69") (pinfunction "TXD6_1_69") (pintype "bidirectional+no_connect"))
    )
    (net (code "66") (name "unconnected-(U15A-TXD6_2-Pad68)") (class "Default")
      (node (ref "U15") (pin "68") (pinfunction "TXD6_2_68") (pintype "bidirectional+no_connect"))
    )
    (net (code "67") (name "unconnected-(U15A-TXD6_3-Pad67)") (class "Default")
      (node (ref "U15") (pin "67") (pinfunction "TXD6_3_67") (pintype "bidirectional+no_connect"))
    )
    (net (code "68") (name "unconnected-(U15A-TXD6_4-Pad55)") (class "Default")
      (node (ref "U15") (pin "55") (pinfunction "TXD6_4_55") (pintype "bidirectional+no_connect"))
    )
    (net (code "69") (name "unconnected-(U15A-TXD6_5-Pad54)") (class "Default")
      (node (ref "U15") (pin "54") (pinfunction "TXD6_5_54") (pintype "bidirectional+no_connect"))
    )
    (net (code "70") (name "unconnected-(U15A-TXD6_6-Pad53)") (class "Default")
      (node (ref "U15") (pin "53") (pinfunction "TXD6_6_53") (pintype "bidirectional+no_connect"))
    )
    (net (code "71") (name "unconnected-(U15A-TXD6_7-Pad52)") (class "Default")
      (node (ref "U15") (pin "52") (pinfunction "TXD6_7_52") (pintype "bidirectional+no_connect"))
    )
    (net (code "72") (name "unconnected-(U15A-TXRX2M_A-Pad13)") (class "Default")
      (node (ref "U15") (pin "13") (pinfunction "TXRX2M_A_13") (pintype "bidirectional+no_connect"))
    )
    (net (code "73") (name "unconnected-(U15A-TXRX2M_B-Pad16)") (class "Default")
      (node (ref "U15") (pin "16") (pinfunction "TXRX2M_B_16") (pintype "bidirectional+no_connect"))
    )
    (net (code "74") (name "unconnected-(U15A-TXRX2M_C-Pad18)") (class "Default")
      (node (ref "U15") (pin "18") (pinfunction "TXRX2M_C_18") (pintype "bidirectional+no_connect"))
    )
    (net (code "75") (name "unconnected-(U15A-TXRX2M_D-Pad21)") (class "Default")
      (node (ref "U15") (pin "21") (pinfunction "TXRX2M_D_21") (pintype "bidirectional+no_connect"))
    )
    (net (code "76") (name "unconnected-(U15A-TXRX2P_A-Pad12)") (class "Default")
      (node (ref "U15") (pin "12") (pinfunction "TXRX2P_A_12") (pintype "bidirectional+no_connect"))
    )
    (net (code "77") (name "unconnected-(U15A-TXRX2P_B-Pad15)") (class "Default")
      (node (ref "U15") (pin "15") (pinfunction "TXRX2P_B_15") (pintype "bidirectional+no_connect"))
    )
    (net (code "78") (name "unconnected-(U15A-TXRX2P_C-Pad17)") (class "Default")
      (node (ref "U15") (pin "17") (pinfunction "TXRX2P_C_17") (pintype "bidirectional+no_connect"))
    )
    (net (code "79") (name "unconnected-(U15A-TXRX2P_D-Pad20)") (class "Default")
      (node (ref "U15") (pin "20") (pinfunction "TXRX2P_D_20") (pintype "bidirectional+no_connect"))
    )
    (net (code "80") (name "unconnected-(U15A-TXRX5M_A-Pad113)") (class "Default")
      (node (ref "U15") (pin "113") (pinfunction "TXRX5M_A_113") (pintype "bidirectional+no_connect"))
    )
    (net (code "81") (name "unconnected-(U15A-TXRX5M_B-Pad116)") (class "Default")
      (node (ref "U15") (pin "116") (pinfunction "TXRX5M_B_116") (pintype "bidirectional+no_connect"))
    )
    (net (code "82") (name "unconnected-(U15A-TXRX5M_C-Pad118)") (class "Default")
      (node (ref "U15") (pin "118") (pinfunction "TXRX5M_C_118") (pintype "bidirectional+no_connect"))
    )
    (net (code "83") (name "unconnected-(U15A-TXRX5M_D-Pad121)") (class "Default")
      (node (ref "U15") (pin "121") (pinfunction "TXRX5M_D_121") (pintype "bidirectional+no_connect"))
    )
    (net (code "84") (name "unconnected-(U15A-TXRX5P_A-Pad112)") (class "Default")
      (node (ref "U15") (pin "112") (pinfunction "TXRX5P_A_112") (pintype "bidirectional+no_connect"))
    )
    (net (code "85") (name "unconnected-(U15A-TXRX5P_B-Pad115)") (class "Default")
      (node (ref "U15") (pin "115") (pinfunction "TXRX5P_B_115") (pintype "bidirectional+no_connect"))
    )
    (net (code "86") (name "unconnected-(U15A-TXRX5P_C-Pad117)") (class "Default")
      (node (ref "U15") (pin "117") (pinfunction "TXRX5P_C_117") (pintype "bidirectional+no_connect"))
    )
    (net (code "87") (name "unconnected-(U15A-TXRX5P_D-Pad120)") (class "Default")
      (node (ref "U15") (pin "120") (pinfunction "TXRX5P_D_120") (pintype "bidirectional+no_connect"))
    )
    (net (code "88") (name "unconnected-(U15A-TX_CLK6{slash}REFCLKI6-Pad63)") (class "Default")
      (node (ref "U15") (pin "63") (pinfunction "TX_CLK6/REFCLKI6_63") (pintype "bidirectional+no_connect"))
    )
    (net (code "89") (name "unconnected-(U15A-TX_EN6{slash}TX_CTL6-Pad64)") (class "Default")
      (node (ref "U15") (pin "64") (pinfunction "TX_EN6/TX_CTL6_64") (pintype "bidirectional+no_connect"))
    )
    (net (code "90") (name "unconnected-(U15A-TX_ER6-Pad65)") (class "Default")
      (node (ref "U15") (pin "65") (pinfunction "TX_ER6_65") (pintype "bidirectional+no_connect"))
    )
    (net (code "91") (name "unconnected-(U15B-NC-Pad46)") (class "Default")
      (node (ref "U15") (pin "46") (pinfunction "NC_46") (pintype "power_in+no_connect"))
    )
    (net (code "92") (name "unconnected-(U15B-NC-Pad61)") (class "Default")
      (node (ref "U15") (pin "61") (pinfunction "NC_61") (pintype "passive+no_connect"))
    )
    (net (code "93") (name "unconnected-(U15B-NC-Pad87)") (class "Default")
      (node (ref "U15") (pin "87") (pinfunction "NC_87") (pintype "passive+no_connect"))
    )
    (net (code "94") (name "unconnected-(U15B-NC-Pad88)") (class "Default")
      (node (ref "U15") (pin "88") (pinfunction "NC_88") (pintype "passive+no_connect"))
    )
    (net (code "95") (name "unconnected-(U15B-NC-Pad93)") (class "Default")
      (node (ref "U15") (pin "93") (pinfunction "NC_93") (pintype "passive+no_connect"))
    )
    (net (code "96") (name "unconnected-(U15B-NC-Pad108)") (class "Default")
      (node (ref "U15") (pin "108") (pinfunction "NC_108") (pintype "passive+no_connect"))
    )
    (net (code "97") (name "unconnected-(U15C-CLKO_25_125-Pad94)") (class "Default")
      (node (ref "U15") (pin "94") (pinfunction "CLKO_25_125_94") (pintype "passive+no_connect"))
    )
    (net (code "98") (name "unconnected-(U15C-SCL{slash}MDC-Pad100)") (class "Default")
      (node (ref "U15") (pin "100") (pinfunction "SCL/MDC_100") (pintype "input+no_connect"))
    )
    (net (code "99") (name "unconnected-(U15C-SDI{slash}SDA{slash}MDIO-Pad97)") (class "Default")
      (node (ref "U15") (pin "97") (pinfunction "SDI/SDA/MDIO_97") (pintype "bidirectional+no_connect"))
    )
    (net (code "100") (name "unconnected-(U15C-SDO-Pad96)") (class "Default")
      (node (ref "U15") (pin "96") (pinfunction "SDO_96") (pintype "output+no_connect"))
    )
    (net (code "101") (name "unconnected-(U15C-~{INTRP}-Pad92)") (class "Default")
      (node (ref "U15") (pin "92") (pinfunction "~{INTRP}_92") (pintype "input+no_connect"))
    )
    (net (code "102") (name "unconnected-(U15C-~{PME}-Pad91)") (class "Default")
      (node (ref "U15") (pin "91") (pinfunction "~{PME}_91") (pintype "input+no_connect"))
    )
    (net (code "103") (name "unconnected-(U15C-~{SCS}-Pad99)") (class "Default")
      (node (ref "U15") (pin "99") (pinfunction "~{SCS}_99") (pintype "input+no_connect"))
    )
  )
)
